# AUDIO.net
KiCad netlist of a schematic drawn in Altium Designer
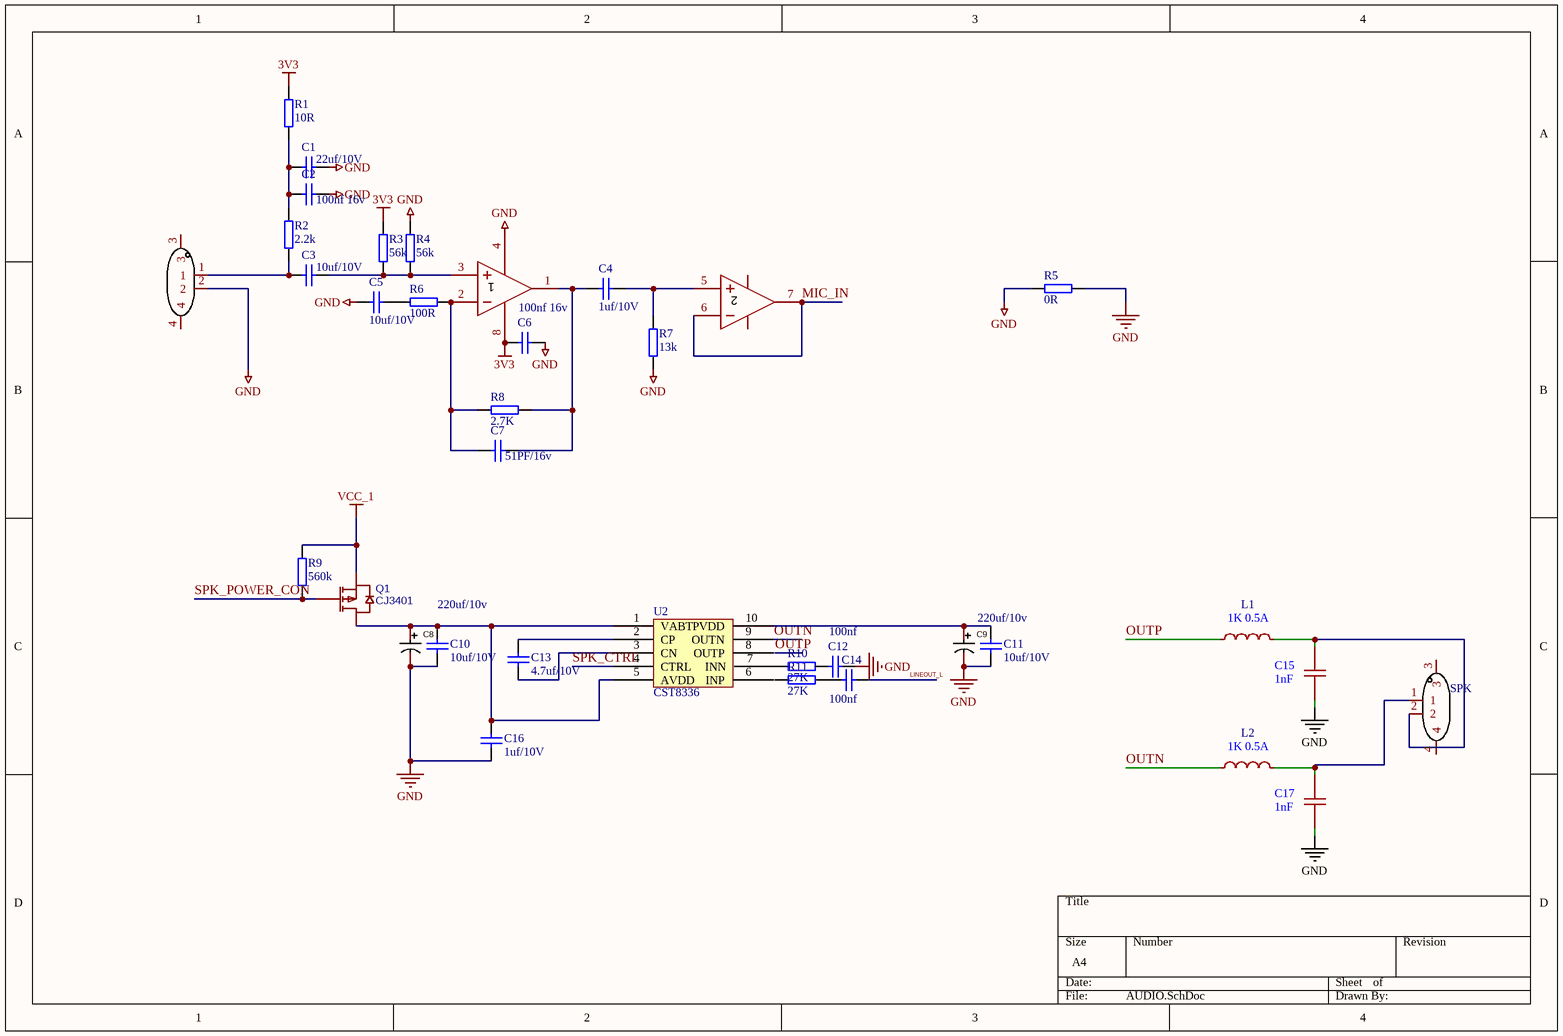
[diagram p0: AUDIO.SchDoc]

(export (version "E")
  (design (tool "Eeschema 10.0.6"))
  (components
    (comp (ref "C1")
      (value "22uf/10V")
      (footprint "0603_C")
      (description "Capacitor")
      (fields (field (name "PUBLISHER") "Altium Limited"))
      (libsource (lib "*") (part "Cap"))
    )
    (comp (ref "C2")
      (value "100nf 16v")
      (footprint "0603_C")
      (description "Capacitor")
      (fields (field (name "PUBLISHER") "Altium Limited"))
      (libsource (lib "*") (part "Cap"))
    )
    (comp (ref "C3")
      (value "10uf/10V")
      (footprint "0603_C")
      (description "Capacitor")
      (fields (field (name "PUBLISHER") "Altium Limited"))
      (libsource (lib "*") (part "Cap"))
    )
    (comp (ref "C4")
      (value "1uf/10V")
      (footprint "0603_C")
      (description "Capacitor")
      (fields (field (name "PUBLISHER") "Altium Limited"))
      (libsource (lib "*") (part "Cap"))
    )
    (comp (ref "C5")
      (value "10uf/10V")
      (footprint "0603_C")
      (description "Capacitor")
      (fields (field (name "PUBLISHER") "Altium Limited"))
      (libsource (lib "*") (part "Cap"))
    )
    (comp (ref "C6")
      (value "100nf 16v")
      (footprint "0603_C")
      (description "Capacitor")
      (fields (field (name "PUBLISHER") "Altium Limited"))
      (libsource (lib "*") (part "Cap"))
    )
    (comp (ref "C7")
      (value "51PF/16v")
      (footprint "0603_C")
      (description "Capacitor")
      (fields (field (name "PUBLISHER") "Altium Limited"))
      (libsource (lib "*") (part "Cap"))
    )
    (comp (ref "C8")
      (value "220uf/10v")
      (footprint "SMD 6.3*7.7")
      (fields (field (name "MANUFACTURER PART") "RVT1A221M0605"))
      (libsource (lib "altium-import") (part "root_0_RVT1A221M0605_C72494_"))
    )
    (comp (ref "C9")
      (value "220uf/10v")
      (footprint "SMD 6.3*7.7")
      (fields (field (name "MANUFACTURER PART") "RVT1A221M0605"))
      (libsource (lib "altium-import") (part "root_0_RVT1A221M0605_C72494_"))
    )
    (comp (ref "C10")
      (value "10uf/10V")
      (footprint "0603_C")
      (description "Capacitor")
      (fields (field (name "PUBLISHER") "Altium Limited"))
      (libsource (lib "*") (part "Cap"))
    )
    (comp (ref "C11")
      (value "10uf/10V")
      (footprint "0603_C")
      (description "Capacitor")
      (fields (field (name "PUBLISHER") "Altium Limited"))
      (libsource (lib "*") (part "Cap"))
    )
    (comp (ref "C12")
      (value "100nf")
      (footprint "0603_C")
      (description "Capacitor")
      (fields (field (name "PUBLISHER") "Altium Limited"))
      (libsource (lib "*") (part "Cap"))
    )
    (comp (ref "C13")
      (value "4.7uf/10V")
      (footprint "0603_C")
      (description "Capacitor")
      (fields (field (name "PUBLISHER") "Altium Limited"))
      (libsource (lib "*") (part "Cap"))
    )
    (comp (ref "C14")
      (value "100nf")
      (footprint "0603_C")
      (description "Capacitor")
      (fields (field (name "PUBLISHER") "Altium Limited"))
      (libsource (lib "*") (part "Cap"))
    )
    (comp (ref "C15")
      (value "1nF")
      (footprint "C0805")
      (libsource (lib "altium-import") (part "root_1_CAP_0805_"))
    )
    (comp (ref "C16")
      (value "1uf/10V")
      (footprint "0603_C")
      (description "Capacitor")
      (fields (field (name "PUBLISHER") "Altium Limited"))
      (libsource (lib "*") (part "Cap"))
    )
    (comp (ref "C17")
      (value "1nF")
      (footprint "C0805")
      (libsource (lib "altium-import") (part "root_1_CAP_0805_"))
    )
    (comp (ref "CON1")
      (value "SPK")
      (footprint "CONN-SMD_2.0-2PLT")
      (fields (field (name "MANUFACTURER PART") "HC-1.25-2PLT"))
      (libsource (lib "altium-import") (part "root_0_HC-1.25-2PLT_"))
    )
    (comp (ref "L1")
      (value "1K 0.5A")
      (footprint "0805_R")
      (fields (field (name "MANUFACTURER PART") "SBK201209T-102Y-N"))
      (libsource (lib "altium-import") (part "root_0_SBK201209T-102Y-N_"))
    )
    (comp (ref "L2")
      (value "1K 0.5A")
      (footprint "0805_R")
      (libsource (lib "altium-import") (part "root_0_SBK201209T-102Y-N_"))
    )
    (comp (ref "MK1")
      (value "~")
      (footprint "SMD_HC-1.25-2PLT")
      (fields (field (name "MANUFACTURER PART") "HC-1.25-2PLT"))
      (libsource (lib "altium-import") (part "root_0_mirrored_HC-1.25-2PLT_"))
    )
    (comp (ref "Q1")
      (value "CJ3401")
      (footprint "SOT-23")
      (fields (field (name "BOM_SUPPLIER PART") "C13799"))
      (libsource (lib "altium-import") (part "root_2_mirrored_CJ3401_"))
    )
    (comp (ref "R1") (value "10R") (footprint "0603_R") (libsource (lib "DIY") (part "RES")))
    (comp (ref "R2") (value "2.2k") (footprint "0603_R") (libsource (lib "DIY") (part "RES")))
    (comp (ref "R3") (value "56k") (footprint "0603_R") (libsource (lib "DIY") (part "RES")))
    (comp (ref "R4") (value "56k") (footprint "0603_R") (libsource (lib "DIY") (part "RES")))
    (comp (ref "R5") (value "0R") (footprint "0603_R") (libsource (lib "DIY") (part "RES")))
    (comp (ref "R6") (value "100R") (footprint "0603_R") (libsource (lib "DIY") (part "RES")))
    (comp (ref "R7") (value "13k") (footprint "0603_R") (libsource (lib "DIY") (part "RES")))
    (comp (ref "R8") (value "2.7K") (footprint "0603_R") (libsource (lib "DIY") (part "RES")))
    (comp (ref "R9") (value "560k") (footprint "0603_R") (libsource (lib "DIY") (part "RES")))
    (comp (ref "R10") (value "27K") (footprint "0603_R") (libsource (lib "DIY") (part "RES")))
    (comp (ref "R11") (value "27K") (footprint "0603_R") (libsource (lib "DIY") (part "RES")))
    (comp (ref "U1")
      (value "lmv358b-sr")
      (footprint "SOP8")
      (fields (field (name "MANUFACTURERPART") "LMV358B-SR"))
      (libsource (lib "altium-import") (part "root_2_mirrored_lmv358b-sr_"))
    )
    (comp (ref "U2") (value "CST8336") (footprint "ESOP-10") (libsource (lib "MyLib") (part "CST8336")))
  )
  (nets
    (net (code "1") (name "/LINEOUT_L") (class "Default")
      (node (ref "C14") (pin "2") (pinfunction "2_2") (pintype "passive"))
    )
    (net (code "2") (name "/MIC_IN") (class "Default")
      (node (ref "U1") (pin "6") (pinfunction "INB-_6") (pintype "passive"))
      (node (ref "U1") (pin "7") (pinfunction "OUTB_7") (pintype "passive"))
    )
    (net (code "3") (name "/OUTN") (class "Default")
      (node (ref "L2") (pin "1") (pinfunction "1_1") (pintype "passive"))
      (node (ref "U2") (pin "9") (pinfunction "OUTN_9") (pintype "passive"))
    )
    (net (code "4") (name "/OUTP") (class "Default")
      (node (ref "L1") (pin "1") (pinfunction "1_1") (pintype "passive"))
    )
    (net (code "5") (name "/SPK_CTRL") (class "Default")
      (node (ref "U2") (pin "4") (pinfunction "CTRL_4") (pintype "passive"))
    )
    (net (code "6") (name "/SPK_POWER_CON") (class "Default")
      (node (ref "Q1") (pin "1") (pinfunction "G_1") (pintype "passive"))
      (node (ref "R9") (pin "2") (pinfunction "2_2") (pintype "passive"))
    )
    (net (code "7") (name "3V3") (class "Default")
      (node (ref "C6") (pin "2") (pinfunction "2_2") (pintype "passive"))
      (node (ref "R1") (pin "2") (pinfunction "2_2") (pintype "passive"))
      (node (ref "R3") (pin "2") (pinfunction "2_2") (pintype "passive"))
      (node (ref "U1") (pin "8") (pinfunction "+VS_8") (pintype "passive"))
    )
    (net (code "8") (name "GND") (class "Default")
      (node (ref "C1") (pin "2") (pinfunction "2_2") (pintype "passive"))
      (node (ref "C10") (pin "2") (pinfunction "2_2") (pintype "passive"))
      (node (ref "C11") (pin "2") (pinfunction "2_2") (pintype "passive"))
      (node (ref "C12") (pin "2") (pinfunction "2_2") (pintype "passive"))
      (node (ref "C15") (pin "1") (pinfunction "1_1") (pintype "passive"))
      (node (ref "C16") (pin "2") (pinfunction "2_2") (pintype "passive"))
      (node (ref "C17") (pin "1") (pinfunction "1_1") (pintype "passive"))
      (node (ref "C2") (pin "2") (pinfunction "2_2") (pintype "passive"))
      (node (ref "C5") (pin "2") (pinfunction "2_2") (pintype "passive"))
      (node (ref "C6") (pin "1") (pinfunction "1_1") (pintype "passive"))
      (node (ref "C8") (pin "2") (pinfunction "2_2") (pintype "passive"))
      (node (ref "C9") (pin "2") (pinfunction "2_2") (pintype "passive"))
      (node (ref "MK1") (pin "2") (pinfunction "2_2") (pintype "passive"))
      (node (ref "R4") (pin "2") (pinfunction "2_2") (pintype "passive"))
      (node (ref "R5") (pin "1") (pinfunction "1_1") (pintype "passive"))
      (node (ref "R5") (pin "2") (pinfunction "2_2") (pintype "passive"))
      (node (ref "R7") (pin "2") (pinfunction "2_2") (pintype "passive"))
      (node (ref "U1") (pin "4") (pinfunction "-VS_4") (pintype "passive"))
    )
    (net (code "9") (name "Net-(C1-Pad1)") (class "Default")
      (node (ref "C1") (pin "1") (pinfunction "1_1") (pintype "passive"))
      (node (ref "C2") (pin "1") (pinfunction "1_1") (pintype "passive"))
      (node (ref "R1") (pin "1") (pinfunction "1_1") (pintype "passive"))
      (node (ref "R2") (pin "2") (pinfunction "2_2") (pintype "passive"))
    )
    (net (code "10") (name "Net-(C3-Pad1)") (class "Default")
      (node (ref "C3") (pin "1") (pinfunction "1_1") (pintype "passive"))
      (node (ref "MK1") (pin "1") (pinfunction "1_1") (pintype "passive"))
      (node (ref "R2") (pin "1") (pinfunction "1_1") (pintype "passive"))
    )
    (net (code "11") (name "Net-(C5-Pad1)") (class "Default")
      (node (ref "C5") (pin "1") (pinfunction "1_1") (pintype "passive"))
      (node (ref "R6") (pin "2") (pinfunction "2_2") (pintype "passive"))
    )
    (net (code "12") (name "Net-(C14-Pad1)") (class "Default")
      (node (ref "C14") (pin "1") (pinfunction "1_1") (pintype "passive"))
      (node (ref "R11") (pin "1") (pinfunction "1_1") (pintype "passive"))
    )
    (net (code "13") (name "Net-(C15-Pad2)") (class "Default")
      (node (ref "C15") (pin "2") (pinfunction "2_2") (pintype "passive"))
      (node (ref "CON1") (pin "2") (pinfunction "2_2") (pintype "passive"))
      (node (ref "L1") (pin "2") (pinfunction "2_2") (pintype "passive"))
    )
    (net (code "14") (name "Net-(C17-Pad2)") (class "Default")
      (node (ref "C17") (pin "2") (pinfunction "2_2") (pintype "passive"))
      (node (ref "CON1") (pin "1") (pinfunction "1_1") (pintype "passive"))
      (node (ref "L2") (pin "2") (pinfunction "2_2") (pintype "passive"))
    )
    (net (code "15") (name "Net-(Q1-D)") (class "Default")
      (node (ref "C10") (pin "1") (pinfunction "1_1") (pintype "passive"))
      (node (ref "C16") (pin "1") (pinfunction "1_1") (pintype "passive"))
      (node (ref "C8") (pin "1") (pinfunction "1_1") (pintype "passive"))
      (node (ref "Q1") (pin "3") (pinfunction "D_3") (pintype "passive"))
      (node (ref "U2") (pin "1") (pinfunction "VABT_1") (pintype "passive"))
      (node (ref "U2") (pin "5") (pinfunction "AVDD_5") (pintype "passive"))
    )
    (net (code "16") (name "Net-(U1A-INA+)") (class "Default")
      (node (ref "C3") (pin "2") (pinfunction "2_2") (pintype "passive"))
      (node (ref "R3") (pin "1") (pinfunction "1_1") (pintype "passive"))
      (node (ref "R4") (pin "1") (pinfunction "1_1") (pintype "passive"))
      (node (ref "U1") (pin "3") (pinfunction "INA+_3") (pintype "passive"))
    )
    (net (code "17") (name "Net-(U1A-INA-)") (class "Default")
      (node (ref "C7") (pin "1") (pinfunction "1_1") (pintype "passive"))
      (node (ref "R6") (pin "1") (pinfunction "1_1") (pintype "passive"))
      (node (ref "R8") (pin "2") (pinfunction "2_2") (pintype "passive"))
      (node (ref "U1") (pin "2") (pinfunction "INA-_2") (pintype "passive"))
    )
    (net (code "18") (name "Net-(U1A-OUTA)") (class "Default")
      (node (ref "C4") (pin "2") (pinfunction "2_2") (pintype "passive"))
      (node (ref "C7") (pin "2") (pinfunction "2_2") (pintype "passive"))
      (node (ref "R8") (pin "1") (pinfunction "1_1") (pintype "passive"))
      (node (ref "U1") (pin "1") (pinfunction "OUTA_1") (pintype "passive"))
    )
    (net (code "19") (name "Net-(U1B-INB+)") (class "Default")
      (node (ref "C4") (pin "1") (pinfunction "1_1") (pintype "passive"))
      (node (ref "R7") (pin "1") (pinfunction "1_1") (pintype "passive"))
      (node (ref "U1") (pin "5") (pinfunction "INB+_5") (pintype "passive"))
    )
    (net (code "20") (name "Net-(U2-CN)") (class "Default")
      (node (ref "C13") (pin "1") (pinfunction "1_1") (pintype "passive"))
      (node (ref "U2") (pin "3") (pinfunction "CN_3") (pintype "passive"))
    )
    (net (code "21") (name "Net-(U2-CP)") (class "Default")
      (node (ref "C13") (pin "2") (pinfunction "2_2") (pintype "passive"))
      (node (ref "U2") (pin "2") (pinfunction "CP_2") (pintype "passive"))
    )
    (net (code "22") (name "Net-(U2-INN)") (class "Default")
      (node (ref "R10") (pin "2") (pinfunction "2_2") (pintype "passive"))
      (node (ref "U2") (pin "7") (pinfunction "INN_7") (pintype "passive"))
    )
    (net (code "23") (name "Net-(U2-PVDD)") (class "Default")
      (node (ref "C11") (pin "1") (pinfunction "1_1") (pintype "passive"))
      (node (ref "C9") (pin "1") (pinfunction "1_1") (pintype "passive"))
      (node (ref "U2") (pin "10") (pinfunction "PVDD_10") (pintype "passive"))
    )
    (net (code "24") (name "VCC_1") (class "Default")
      (node (ref "Q1") (pin "2") (pinfunction "S_2") (pintype "passive"))
      (node (ref "R9") (pin "1") (pinfunction "1_1") (pintype "passive"))
    )
    (net (code "25") (name "unconnected-(C12-Pad1)") (class "Default")
      (node (ref "C12") (pin "1") (pinfunction "1_1") (pintype "passive"))
    )
    (net (code "26") (name "unconnected-(CON1-Pad3)") (class "Default")
      (node (ref "CON1") (pin "3") (pinfunction "3_3") (pintype "passive"))
    )
    (net (code "27") (name "unconnected-(CON1-Pad4)") (class "Default")
      (node (ref "CON1") (pin "4") (pinfunction "4_4") (pintype "passive"))
    )
    (net (code "28") (name "unconnected-(MK1-Pad3)") (class "Default")
      (node (ref "MK1") (pin "3") (pinfunction "3_3") (pintype "passive"))
    )
    (net (code "29") (name "unconnected-(MK1-Pad4)") (class "Default")
      (node (ref "MK1") (pin "4") (pinfunction "4_4") (pintype "passive"))
    )
    (net (code "30") (name "unconnected-(R10-Pad1)") (class "Default")
      (node (ref "R10") (pin "1") (pinfunction "1_1") (pintype "passive"))
    )
    (net (code "31") (name "unconnected-(R11-Pad2)") (class "Default")
      (node (ref "R11") (pin "2") (pinfunction "2_2") (pintype "passive"))
    )
    (net (code "32") (name "unconnected-(U2-INP-Pad6)") (class "Default")
      (node (ref "U2") (pin "6") (pinfunction "INP_6") (pintype "passive"))
    )
    (net (code "33") (name "unconnected-(U2-OUTP-Pad8)") (class "Default")
      (node (ref "U2") (pin "8") (pinfunction "OUTP_8") (pintype "passive"))
    )
  )
)
